# AirValveDriver.net
KiCad netlist of a schematic drawn in EAGLE
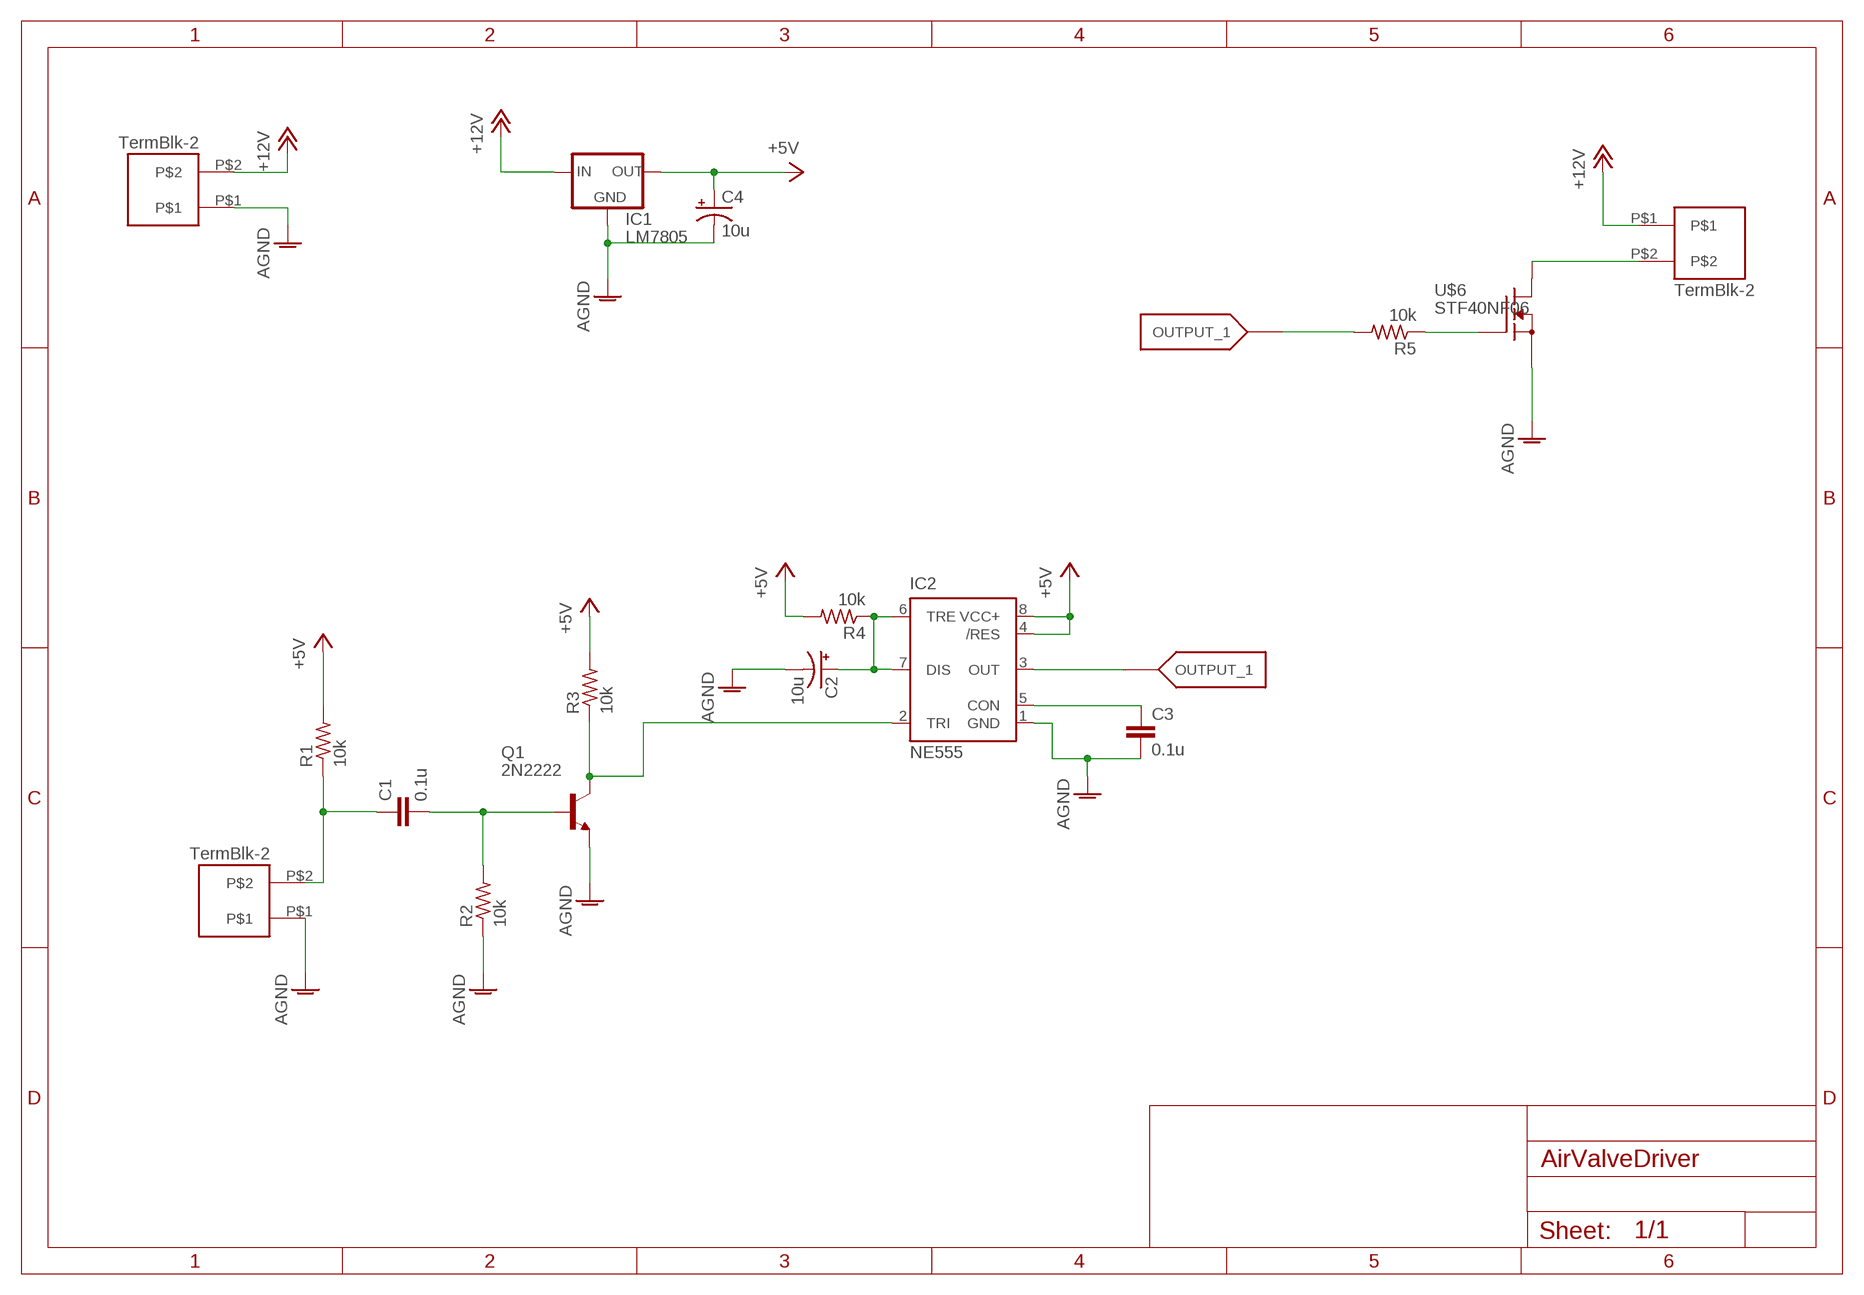
[diagram p0: schematic, sheet 1]

(export (version "E")
  (design (tool "Eeschema 10.0.6"))
  (components
    (comp (ref "C1")
      (value "0.1u")
      (footprint "eagle-import:CCERAMIC_PKG")
      (libsource (lib "eagle-import") (part "CAPACITOR_CERAMIC"))
    )
    (comp (ref "C2")
      (value "10u")
      (footprint "eagle-import:CPOL_PKG")
      (libsource (lib "eagle-import") (part "CAPACITOR_POLARIZED"))
    )
    (comp (ref "C3")
      (value "0.1u")
      (footprint "eagle-import:CCERAMIC_PKG")
      (libsource (lib "eagle-import") (part "CAPACITOR_CERAMIC"))
    )
    (comp (ref "C4")
      (value "10u")
      (footprint "eagle-import:CPOL_PKG")
      (libsource (lib "eagle-import") (part "CAPACITOR_POLARIZED"))
    )
    (comp (ref "IC1")
      (value "LM7805")
      (footprint "eagle-import:78XXL")
      (libsource (lib "eagle-import") (part "78XXL"))
    )
    (comp (ref "IC2")
      (value "NE555")
      (footprint "eagle-import:DIL-08")
      (fields (field (name "MF") "Arrow Electronics") (field (name "MPN") "NE555N"))
      (libsource (lib "eagle-import") (part "NE555"))
    )
    (comp (ref "Q1")
      (value "2N2222")
      (footprint "eagle-import:TO18")
      (libsource (lib "eagle-import") (part "2N2222"))
    )
    (comp (ref "R1")
      (value "10k")
      (footprint "eagle-import:RESISTOR_PKG")
      (libsource (lib "eagle-import") (part "RESISTOR"))
    )
    (comp (ref "R2")
      (value "10k")
      (footprint "eagle-import:RESISTOR_PKG")
      (libsource (lib "eagle-import") (part "RESISTOR"))
    )
    (comp (ref "R3")
      (value "10k")
      (footprint "eagle-import:RESISTOR_PKG")
      (libsource (lib "eagle-import") (part "RESISTOR"))
    )
    (comp (ref "R4")
      (value "10k")
      (footprint "eagle-import:RESISTOR_PKG")
      (libsource (lib "eagle-import") (part "RESISTOR"))
    )
    (comp (ref "R5")
      (value "10k")
      (footprint "eagle-import:RESISTOR_PKG")
      (libsource (lib "eagle-import") (part "RESISTOR"))
    )
    (comp (ref "U$2")
      (value "TB2")
      (footprint "eagle-import:TB2_PKG")
      (libsource (lib "eagle-import") (part "TB2"))
    )
    (comp (ref "U$3")
      (value "Pwr")
      (footprint "eagle-import:TB2_PKG")
      (libsource (lib "eagle-import") (part "TB2"))
    )
    (comp (ref "U$5")
      (value "TB2")
      (footprint "eagle-import:TB2_PKG")
      (libsource (lib "eagle-import") (part "TB2"))
    )
    (comp (ref "U$6")
      (value "STF40NF06")
      (footprint "eagle-import:TO220H")
      (libsource (lib "eagle-import") (part "STF40NF06"))
    )
  )
  (nets
    (net (code "1") (name "+5V") (class "Default")
      (node (ref "C4") (pin "+") (pinfunction "+_+") (pintype "passive"))
      (node (ref "IC1") (pin "OUT") (pinfunction "OUT_OUT") (pintype "passive"))
      (node (ref "IC2") (pin "4") (pinfunction "/RES_4") (pintype "input"))
      (node (ref "IC2") (pin "8") (pinfunction "VCC+_8") (pintype "power_in"))
      (node (ref "R1") (pin "2") (pinfunction "2_2") (pintype "passive"))
      (node (ref "R3") (pin "2") (pinfunction "2_2") (pintype "passive"))
      (node (ref "R4") (pin "2") (pinfunction "2_2") (pintype "passive"))
    )
    (net (code "2") (name "+12V") (class "Default")
      (node (ref "IC1") (pin "IN") (pinfunction "IN_IN") (pintype "input"))
      (node (ref "U$2") (pin "P$1") (pinfunction "P$1_P$1") (pintype "bidirectional"))
      (node (ref "U$3") (pin "P$2") (pinfunction "P$2_P$2") (pintype "bidirectional"))
    )
    (net (code "3") (name "AGND") (class "Default")
      (node (ref "C2") (pin "-") (pinfunction "-_-") (pintype "passive"))
      (node (ref "C3") (pin "2") (pinfunction "2_2") (pintype "passive"))
      (node (ref "C4") (pin "-") (pinfunction "-_-") (pintype "passive"))
      (node (ref "IC1") (pin "GND") (pinfunction "GND_GND") (pintype "input"))
      (node (ref "IC2") (pin "1") (pinfunction "GND_1") (pintype "power_in"))
      (node (ref "Q1") (pin "1") (pinfunction "E_1") (pintype "passive"))
      (node (ref "R2") (pin "1") (pinfunction "1_1") (pintype "passive"))
      (node (ref "U$3") (pin "P$1") (pinfunction "P$1_P$1") (pintype "bidirectional"))
      (node (ref "U$5") (pin "P$1") (pinfunction "P$1_P$1") (pintype "bidirectional"))
      (node (ref "U$6") (pin "3") (pinfunction "S_3") (pintype "passive"))
    )
    (net (code "4") (name "Net-(C1-Pad1)") (class "Default")
      (node (ref "C1") (pin "1") (pinfunction "1_1") (pintype "passive"))
      (node (ref "R1") (pin "1") (pinfunction "1_1") (pintype "passive"))
      (node (ref "U$5") (pin "P$2") (pinfunction "P$2_P$2") (pintype "bidirectional"))
    )
    (net (code "5") (name "Net-(IC2-CON)") (class "Default")
      (node (ref "C3") (pin "1") (pinfunction "1_1") (pintype "passive"))
      (node (ref "IC2") (pin "5") (pinfunction "CON_5") (pintype "input"))
    )
    (net (code "6") (name "Net-(IC2-DIS)") (class "Default")
      (node (ref "C2") (pin "+") (pinfunction "+_+") (pintype "passive"))
      (node (ref "IC2") (pin "6") (pinfunction "TRE_6") (pintype "input"))
      (node (ref "IC2") (pin "7") (pinfunction "DIS_7") (pintype "input"))
      (node (ref "R4") (pin "1") (pinfunction "1_1") (pintype "passive"))
    )
    (net (code "7") (name "Net-(IC2-TRI)") (class "Default")
      (node (ref "IC2") (pin "2") (pinfunction "TRI_2") (pintype "input"))
      (node (ref "Q1") (pin "3") (pinfunction "C_3") (pintype "passive"))
      (node (ref "R3") (pin "1") (pinfunction "1_1") (pintype "passive"))
    )
    (net (code "8") (name "Net-(Q1-B)") (class "Default")
      (node (ref "C1") (pin "2") (pinfunction "2_2") (pintype "passive"))
      (node (ref "Q1") (pin "2") (pinfunction "B_2") (pintype "passive"))
      (node (ref "R2") (pin "2") (pinfunction "2_2") (pintype "passive"))
    )
    (net (code "9") (name "Net-(U$6-D)") (class "Default")
      (node (ref "U$2") (pin "P$2") (pinfunction "P$2_P$2") (pintype "bidirectional"))
      (node (ref "U$6") (pin "2") (pinfunction "D_2") (pintype "passive"))
    )
    (net (code "10") (name "Net-(U$6-G)") (class "Default")
      (node (ref "R5") (pin "1") (pinfunction "1_1") (pintype "passive"))
      (node (ref "U$6") (pin "1") (pinfunction "G_1") (pintype "passive"))
    )
    (net (code "11") (name "OUTPUT_1") (class "Default")
      (node (ref "IC2") (pin "3") (pinfunction "OUT_3") (pintype "output"))
      (node (ref "R5") (pin "2") (pinfunction "2_2") (pintype "passive"))
    )
  )
)
